# Lift2.net
KiCad netlist of a schematic drawn in EAGLE
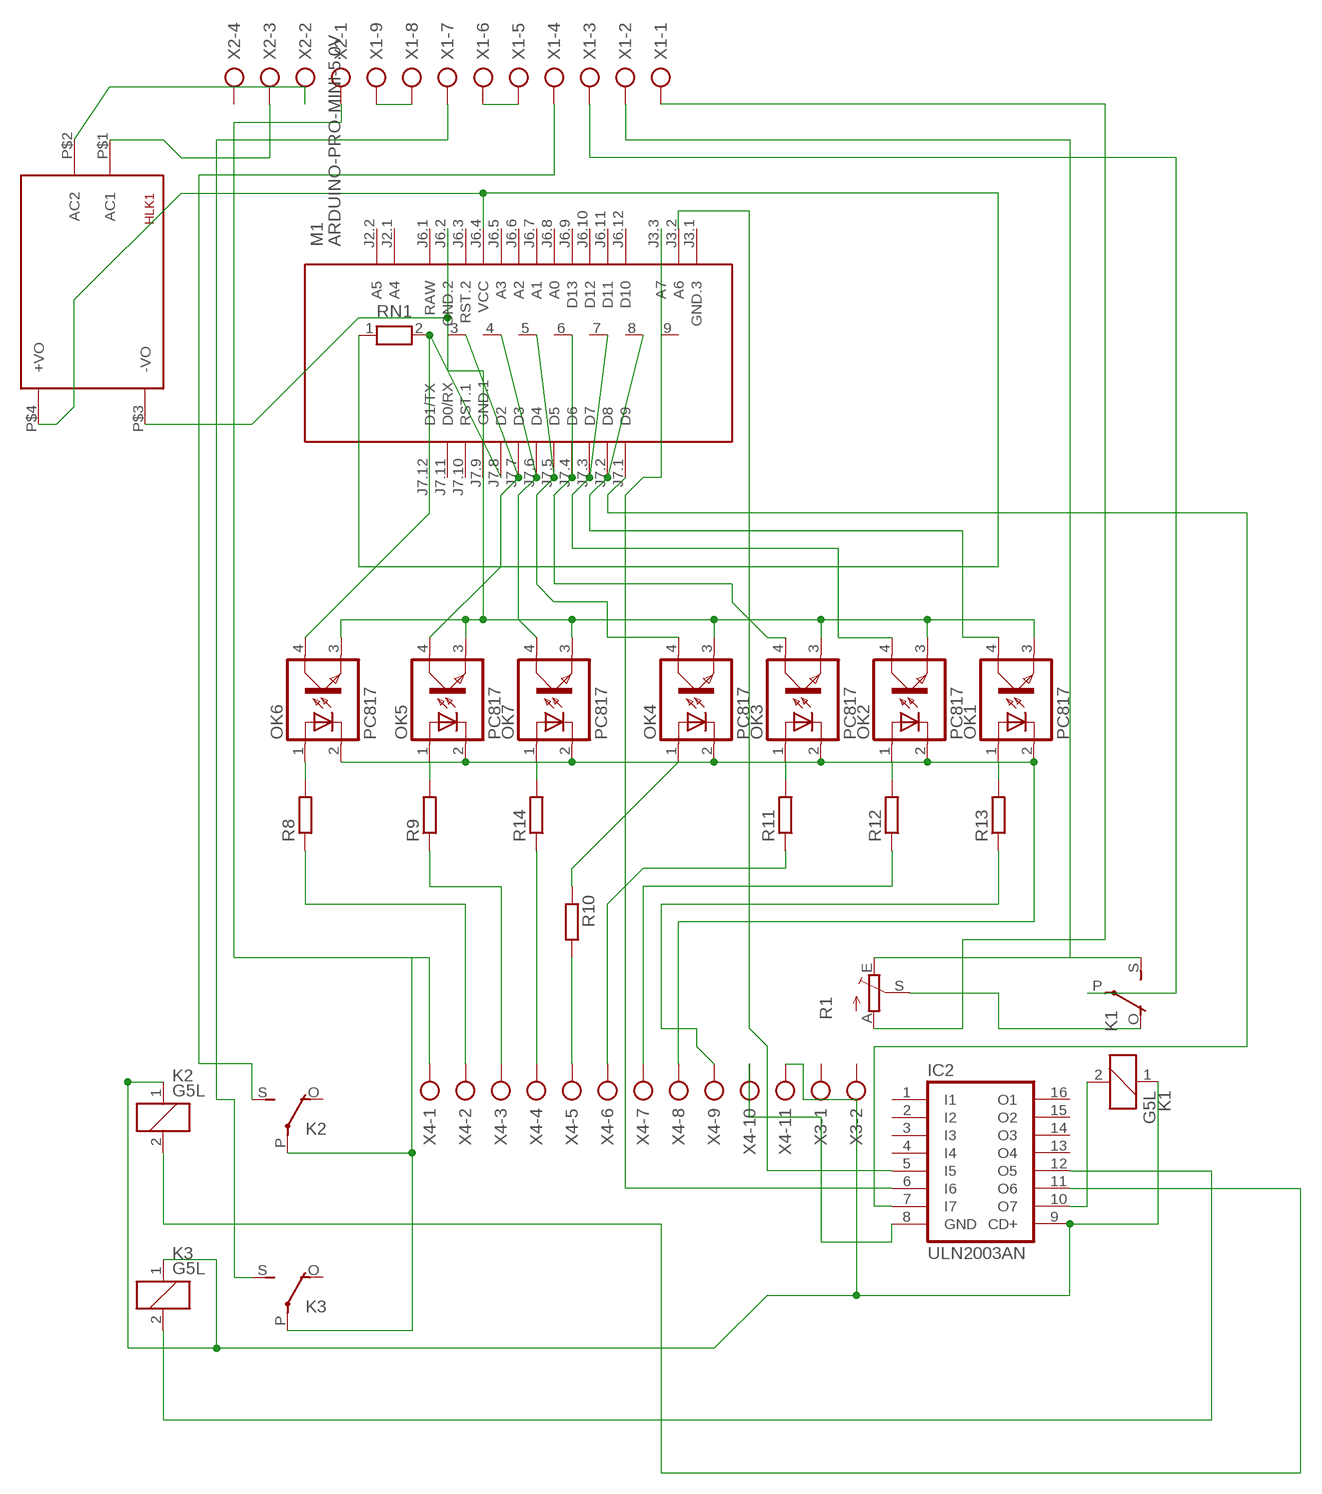
[diagram p0: schematic, sheet 1]

(export (version "E")
  (design (tool "Eeschema 10.0.6"))
  (components
    (comp (ref "HLK1")
      (value "HLK-PM013W")
      (footprint "eagle-import:HLK-PM01")
      (libsource (lib "eagle-import") (part "HLK-PM013W"))
    )
    (comp (ref "IC2")
      (value "ULN2003AN")
      (footprint "eagle-import:DIL16")
      (libsource (lib "eagle-import") (part "ULN2003AN"))
    )
    (comp (ref "K1")
      (value "G5L")
      (footprint "eagle-import:G5LE")
      (libsource (lib "eagle-import") (part "G5L"))
    )
    (comp (ref "K2")
      (value "G5L")
      (footprint "eagle-import:G5LE")
      (libsource (lib "eagle-import") (part "G5L"))
    )
    (comp (ref "K3")
      (value "G5L")
      (footprint "eagle-import:G5LE")
      (libsource (lib "eagle-import") (part "G5L"))
    )
    (comp (ref "M1")
      (value "ARDUINO-PRO-MINI-5.0V")
      (footprint "eagle-import:ARDUINO-PRO-MINI")
      (libsource (lib "eagle-import") (part "ARDUINO-PRO-MINI-5.0V"))
    )
    (comp (ref "OK1")
      (value "PC817")
      (footprint "eagle-import:DIL04")
      (fields (field (name "MPN") "PC817X4J000F"))
      (libsource (lib "eagle-import") (part "PC817"))
    )
    (comp (ref "OK2")
      (value "PC817")
      (footprint "eagle-import:DIL04")
      (fields (field (name "MPN") "PC817X4J000F"))
      (libsource (lib "eagle-import") (part "PC817"))
    )
    (comp (ref "OK3")
      (value "PC817")
      (footprint "eagle-import:DIL04")
      (fields (field (name "MPN") "PC817X4J000F"))
      (libsource (lib "eagle-import") (part "PC817"))
    )
    (comp (ref "OK4")
      (value "PC817")
      (footprint "eagle-import:DIL04")
      (fields (field (name "MPN") "PC817X4J000F"))
      (libsource (lib "eagle-import") (part "PC817"))
    )
    (comp (ref "OK5")
      (value "PC817")
      (footprint "eagle-import:DIL04")
      (fields (field (name "MPN") "PC817X4J000F"))
      (libsource (lib "eagle-import") (part "PC817"))
    )
    (comp (ref "OK6")
      (value "PC817")
      (footprint "eagle-import:DIL04")
      (fields (field (name "MPN") "PC817X4J000F"))
      (libsource (lib "eagle-import") (part "PC817"))
    )
    (comp (ref "OK7")
      (value "PC817")
      (footprint "eagle-import:DIL04")
      (fields (field (name "MPN") "PC817X4J000F"))
      (libsource (lib "eagle-import") (part "PC817"))
    )
    (comp (ref "R1")
      (value "TRIM_EU-CA6V")
      (footprint "eagle-import:CA6V")
      (libsource (lib "eagle-import") (part "TRIM_EU-CA6V"))
    )
    (comp (ref "R8")
      (value "R-EU_0204/7")
      (footprint "eagle-import:0204_7")
      (libsource (lib "eagle-import") (part "R-EU_0204/7"))
    )
    (comp (ref "R9")
      (value "R-EU_0204/7")
      (footprint "eagle-import:0204_7")
      (libsource (lib "eagle-import") (part "R-EU_0204/7"))
    )
    (comp (ref "R10")
      (value "R-EU_0204/7")
      (footprint "eagle-import:0204_7")
      (libsource (lib "eagle-import") (part "R-EU_0204/7"))
    )
    (comp (ref "R11")
      (value "R-EU_0204/7")
      (footprint "eagle-import:0204_7")
      (libsource (lib "eagle-import") (part "R-EU_0204/7"))
    )
    (comp (ref "R12")
      (value "R-EU_0204/7")
      (footprint "eagle-import:0204_7")
      (libsource (lib "eagle-import") (part "R-EU_0204/7"))
    )
    (comp (ref "R13")
      (value "R-EU_0204/7")
      (footprint "eagle-import:0204_7")
      (libsource (lib "eagle-import") (part "R-EU_0204/7"))
    )
    (comp (ref "R14")
      (value "R-EU_0204/7")
      (footprint "eagle-import:0204_7")
      (libsource (lib "eagle-import") (part "R-EU_0204/7"))
    )
    (comp (ref "RN1")
      (value "RN08")
      (footprint "eagle-import:RN-9")
      (libsource (lib "eagle-import") (part "RN08"))
    )
    (comp (ref "X1")
      (value "AK300/9")
      (footprint "eagle-import:AK300_9")
      (libsource (lib "eagle-import") (part "AK300/9"))
    )
    (comp (ref "X2")
      (value "AK300/4")
      (footprint "eagle-import:AK300_4")
      (libsource (lib "eagle-import") (part "AK300/4"))
    )
    (comp (ref "X3")
      (value "AK300/2")
      (footprint "eagle-import:AK300_2")
      (libsource (lib "eagle-import") (part "AK300/2"))
    )
    (comp (ref "X4")
      (value "AK300/11")
      (footprint "eagle-import:AK300_11")
      (libsource (lib "eagle-import") (part "AK300/11"))
    )
  )
  (nets
    (net (code "1") (name "/RAW") (class "Default")
      (node (ref "M1") (pin "J6.1") (pinfunction "RAW_J6.1") (pintype "power_in"))
    )
    (net (code "2") (name "Net-(HLK1-+VO)") (class "Default")
      (node (ref "HLK1") (pin "P$4") (pinfunction "+VO_P$4") (pintype "bidirectional"))
      (node (ref "M1") (pin "J6.4") (pinfunction "VCC_J6.4") (pintype "power_in"))
      (node (ref "RN1") (pin "1") (pinfunction "1_1") (pintype "passive"))
    )
    (net (code "3") (name "Net-(HLK1--VO)") (class "Default")
      (node (ref "HLK1") (pin "P$3") (pinfunction "-VO_P$3") (pintype "bidirectional"))
      (node (ref "M1") (pin "J6.2") (pinfunction "GND.2_J6.2") (pintype "power_in"))
      (node (ref "M1") (pin "J7.9") (pinfunction "GND.1_J7.9") (pintype "power_in"))
      (node (ref "OK1") (pin "3") (pinfunction "EMIT_3") (pintype "passive"))
      (node (ref "OK2") (pin "3") (pinfunction "EMIT_3") (pintype "passive"))
      (node (ref "OK3") (pin "3") (pinfunction "EMIT_3") (pintype "passive"))
      (node (ref "OK4") (pin "3") (pinfunction "EMIT_3") (pintype "passive"))
      (node (ref "OK5") (pin "3") (pinfunction "EMIT_3") (pintype "passive"))
      (node (ref "OK6") (pin "3") (pinfunction "EMIT_3") (pintype "passive"))
      (node (ref "OK7") (pin "3") (pinfunction "EMIT_3") (pintype "passive"))
    )
    (net (code "4") (name "Net-(HLK1-AC1)") (class "Default")
      (node (ref "HLK1") (pin "P$1") (pinfunction "AC1_P$1") (pintype "bidirectional"))
      (node (ref "X2") (pin "3") (pinfunction "KL_3") (pintype "passive"))
    )
    (net (code "5") (name "Net-(HLK1-AC2)") (class "Default")
      (node (ref "HLK1") (pin "P$2") (pinfunction "AC2_P$2") (pintype "bidirectional"))
      (node (ref "X2") (pin "2") (pinfunction "KL_2") (pintype "passive"))
    )
    (net (code "6") (name "Net-(IC2-CD+)") (class "Default")
      (node (ref "IC2") (pin "9") (pinfunction "CD+_9") (pintype "passive"))
      (node (ref "K1") (pin "1") (pinfunction "1_1") (pintype "passive"))
      (node (ref "K2") (pin "1") (pinfunction "1_1") (pintype "passive"))
      (node (ref "K3") (pin "1") (pinfunction "1_1") (pintype "passive"))
      (node (ref "X4") (pin "11") (pinfunction "KL_11") (pintype "passive"))
    )
    (net (code "7") (name "Net-(IC2-GND)") (class "Default")
      (node (ref "IC2") (pin "8") (pinfunction "GND_8") (pintype "power_in"))
      (node (ref "X4") (pin "10") (pinfunction "KL_10") (pintype "passive"))
    )
    (net (code "8") (name "Net-(IC2-I5)") (class "Default")
      (node (ref "IC2") (pin "5") (pinfunction "I5_5") (pintype "input"))
      (node (ref "M1") (pin "J3.2") (pinfunction "A6_J3.2") (pintype "bidirectional"))
    )
    (net (code "9") (name "Net-(IC2-I6)") (class "Default")
      (node (ref "IC2") (pin "6") (pinfunction "I6_6") (pintype "input"))
      (node (ref "M1") (pin "J3.3") (pinfunction "A7_J3.3") (pintype "bidirectional"))
    )
    (net (code "10") (name "Net-(IC2-I7)") (class "Default")
      (node (ref "IC2") (pin "7") (pinfunction "I7_7") (pintype "input"))
      (node (ref "M1") (pin "J7.1") (pinfunction "D9_J7.1") (pintype "bidirectional"))
    )
    (net (code "11") (name "Net-(IC2-O5)") (class "Default")
      (node (ref "IC2") (pin "12") (pinfunction "O5_12") (pintype "open_collector"))
      (node (ref "K3") (pin "2") (pinfunction "2_2") (pintype "passive"))
    )
    (net (code "12") (name "Net-(IC2-O6)") (class "Default")
      (node (ref "IC2") (pin "11") (pinfunction "O6_11") (pintype "open_collector"))
      (node (ref "K2") (pin "2") (pinfunction "2_2") (pintype "passive"))
    )
    (net (code "13") (name "Net-(IC2-O7)") (class "Default")
      (node (ref "IC2") (pin "10") (pinfunction "O7_10") (pintype "open_collector"))
      (node (ref "K1") (pin "2") (pinfunction "2_2") (pintype "passive"))
    )
    (net (code "14") (name "Net-(K1-PadO)") (class "Default")
      (node (ref "K1") (pin "O") (pinfunction "O_O") (pintype "passive"))
      (node (ref "R1") (pin "S") (pinfunction "S_S") (pintype "passive"))
    )
    (net (code "15") (name "Net-(M1-D2)") (class "Default")
      (node (ref "M1") (pin "J7.8") (pinfunction "D2_J7.8") (pintype "bidirectional"))
      (node (ref "OK6") (pin "4") (pinfunction "COL_4") (pintype "passive"))
      (node (ref "RN1") (pin "2") (pinfunction "2_2") (pintype "passive"))
    )
    (net (code "16") (name "Net-(M1-D3)") (class "Default")
      (node (ref "M1") (pin "J7.7") (pinfunction "D3_J7.7") (pintype "bidirectional"))
      (node (ref "OK5") (pin "4") (pinfunction "COL_4") (pintype "passive"))
      (node (ref "RN1") (pin "3") (pinfunction "3_3") (pintype "passive"))
    )
    (net (code "17") (name "Net-(M1-D4)") (class "Default")
      (node (ref "M1") (pin "J7.6") (pinfunction "D4_J7.6") (pintype "bidirectional"))
      (node (ref "OK7") (pin "4") (pinfunction "COL_4") (pintype "passive"))
      (node (ref "RN1") (pin "4") (pinfunction "4_4") (pintype "passive"))
    )
    (net (code "18") (name "Net-(M1-D5)") (class "Default")
      (node (ref "M1") (pin "J7.5") (pinfunction "D5_J7.5") (pintype "bidirectional"))
      (node (ref "OK4") (pin "4") (pinfunction "COL_4") (pintype "passive"))
      (node (ref "RN1") (pin "5") (pinfunction "5_5") (pintype "passive"))
    )
    (net (code "19") (name "Net-(M1-D6)") (class "Default")
      (node (ref "M1") (pin "J7.4") (pinfunction "D6_J7.4") (pintype "bidirectional"))
      (node (ref "OK3") (pin "4") (pinfunction "COL_4") (pintype "passive"))
      (node (ref "RN1") (pin "6") (pinfunction "6_6") (pintype "passive"))
    )
    (net (code "20") (name "Net-(M1-D7)") (class "Default")
      (node (ref "M1") (pin "J7.3") (pinfunction "D7_J7.3") (pintype "bidirectional"))
      (node (ref "OK2") (pin "4") (pinfunction "COL_4") (pintype "passive"))
      (node (ref "RN1") (pin "7") (pinfunction "7_7") (pintype "passive"))
    )
    (net (code "21") (name "Net-(M1-D8)") (class "Default")
      (node (ref "M1") (pin "J7.2") (pinfunction "D8_J7.2") (pintype "bidirectional"))
      (node (ref "OK1") (pin "4") (pinfunction "COL_4") (pintype "passive"))
      (node (ref "RN1") (pin "8") (pinfunction "8_8") (pintype "passive"))
    )
    (net (code "22") (name "Net-(OK1-A)") (class "Default")
      (node (ref "OK1") (pin "1") (pinfunction "A_1") (pintype "passive"))
      (node (ref "R13") (pin "2") (pinfunction "2_2") (pintype "passive"))
    )
    (net (code "23") (name "Net-(OK1-C)") (class "Default")
      (node (ref "OK1") (pin "2") (pinfunction "C_2") (pintype "passive"))
      (node (ref "OK2") (pin "2") (pinfunction "C_2") (pintype "passive"))
      (node (ref "OK3") (pin "2") (pinfunction "C_2") (pintype "passive"))
      (node (ref "OK4") (pin "2") (pinfunction "C_2") (pintype "passive"))
      (node (ref "OK5") (pin "2") (pinfunction "C_2") (pintype "passive"))
      (node (ref "OK6") (pin "2") (pinfunction "C_2") (pintype "passive"))
      (node (ref "OK7") (pin "2") (pinfunction "C_2") (pintype "passive"))
      (node (ref "X4") (pin "8") (pinfunction "KL_8") (pintype "passive"))
    )
    (net (code "24") (name "Net-(OK2-A)") (class "Default")
      (node (ref "OK2") (pin "1") (pinfunction "A_1") (pintype "passive"))
      (node (ref "R12") (pin "2") (pinfunction "2_2") (pintype "passive"))
    )
    (net (code "25") (name "Net-(OK3-A)") (class "Default")
      (node (ref "OK3") (pin "1") (pinfunction "A_1") (pintype "passive"))
      (node (ref "R11") (pin "2") (pinfunction "2_2") (pintype "passive"))
    )
    (net (code "26") (name "Net-(OK4-A)") (class "Default")
      (node (ref "OK4") (pin "1") (pinfunction "A_1") (pintype "passive"))
      (node (ref "R10") (pin "1") (pinfunction "1_1") (pintype "passive"))
    )
    (net (code "27") (name "Net-(OK5-A)") (class "Default")
      (node (ref "OK5") (pin "1") (pinfunction "A_1") (pintype "passive"))
      (node (ref "R9") (pin "2") (pinfunction "2_2") (pintype "passive"))
    )
    (net (code "28") (name "Net-(OK6-A)") (class "Default")
      (node (ref "OK6") (pin "1") (pinfunction "A_1") (pintype "passive"))
      (node (ref "R8") (pin "2") (pinfunction "2_2") (pintype "passive"))
    )
    (net (code "29") (name "Net-(OK7-A)") (class "Default")
      (node (ref "OK7") (pin "1") (pinfunction "A_1") (pintype "passive"))
      (node (ref "R14") (pin "2") (pinfunction "2_2") (pintype "passive"))
    )
    (net (code "30") (name "Net-(X1A-KL)") (class "Default")
      (node (ref "R1") (pin "A") (pinfunction "A_A") (pintype "passive"))
      (node (ref "X1") (pin "1") (pinfunction "KL_1") (pintype "passive"))
    )
    (net (code "31") (name "Net-(X1B-KL)") (class "Default")
      (node (ref "K1") (pin "S") (pinfunction "S_S") (pintype "passive"))
      (node (ref "R1") (pin "E") (pinfunction "E_E") (pintype "passive"))
      (node (ref "X1") (pin "2") (pinfunction "KL_2") (pintype "passive"))
    )
    (net (code "32") (name "Net-(X1C-KL)") (class "Default")
      (node (ref "K1") (pin "P") (pinfunction "P_P") (pintype "passive"))
      (node (ref "X1") (pin "3") (pinfunction "KL_3") (pintype "passive"))
    )
    (net (code "33") (name "Net-(X1D-KL)") (class "Default")
      (node (ref "K2") (pin "S") (pinfunction "S_S") (pintype "passive"))
      (node (ref "X1") (pin "4") (pinfunction "KL_4") (pintype "passive"))
    )
    (net (code "34") (name "Net-(X1E-KL)") (class "Default")
      (node (ref "X1") (pin "5") (pinfunction "KL_5") (pintype "passive"))
      (node (ref "X1") (pin "6") (pinfunction "KL_6") (pintype "passive"))
    )
    (net (code "35") (name "Net-(X1G-KL)") (class "Default")
      (node (ref "K3") (pin "S") (pinfunction "S_S") (pintype "passive"))
      (node (ref "X1") (pin "7") (pinfunction "KL_7") (pintype "passive"))
    )
    (net (code "36") (name "Net-(X1H-KL)") (class "Default")
      (node (ref "X1") (pin "8") (pinfunction "KL_8") (pintype "passive"))
      (node (ref "X1") (pin "9") (pinfunction "KL_9") (pintype "passive"))
    )
    (net (code "37") (name "Net-(X2A-KL)") (class "Default")
      (node (ref "K2") (pin "P") (pinfunction "P_P") (pintype "passive"))
      (node (ref "K3") (pin "P") (pinfunction "P_P") (pintype "passive"))
      (node (ref "X2") (pin "1") (pinfunction "KL_1") (pintype "passive"))
      (node (ref "X4") (pin "1") (pinfunction "KL_1") (pintype "passive"))
    )
    (net (code "38") (name "Net-(X4D-KL)") (class "Default")
      (node (ref "R8") (pin "1") (pinfunction "1_1") (pintype "passive"))
      (node (ref "X4") (pin "2") (pinfunction "KL_2") (pintype "passive"))
    )
    (net (code "39") (name "Net-(X4E-KL)") (class "Default")
      (node (ref "R9") (pin "1") (pinfunction "1_1") (pintype "passive"))
      (node (ref "X4") (pin "3") (pinfunction "KL_3") (pintype "passive"))
    )
    (net (code "40") (name "Net-(X4F-KL)") (class "Default")
      (node (ref "R14") (pin "1") (pinfunction "1_1") (pintype "passive"))
      (node (ref "X4") (pin "4") (pinfunction "KL_4") (pintype "passive"))
    )
    (net (code "41") (name "Net-(X4G-KL)") (class "Default")
      (node (ref "R10") (pin "2") (pinfunction "2_2") (pintype "passive"))
      (node (ref "X4") (pin "5") (pinfunction "KL_5") (pintype "passive"))
    )
    (net (code "42") (name "Net-(X4H-KL)") (class "Default")
      (node (ref "R11") (pin "1") (pinfunction "1_1") (pintype "passive"))
      (node (ref "X4") (pin "6") (pinfunction "KL_6") (pintype "passive"))
    )
    (net (code "43") (name "Net-(X4I-KL)") (class "Default")
      (node (ref "R12") (pin "1") (pinfunction "1_1") (pintype "passive"))
      (node (ref "X4") (pin "7") (pinfunction "KL_7") (pintype "passive"))
    )
    (net (code "44") (name "Net-(X4K-KL)") (class "Default")
      (node (ref "R13") (pin "1") (pinfunction "1_1") (pintype "passive"))
      (node (ref "X4") (pin "9") (pinfunction "KL_9") (pintype "passive"))
    )
    (net (code "45") (name "unconnected-(IC2-I1-Pad1)") (class "Default")
      (node (ref "IC2") (pin "1") (pinfunction "I1_1") (pintype "input"))
    )
    (net (code "46") (name "unconnected-(IC2-I2-Pad2)") (class "Default")
      (node (ref "IC2") (pin "2") (pinfunction "I2_2") (pintype "input"))
    )
    (net (code "47") (name "unconnected-(IC2-I3-Pad3)") (class "Default")
      (node (ref "IC2") (pin "3") (pinfunction "I3_3") (pintype "input"))
    )
    (net (code "48") (name "unconnected-(IC2-I4-Pad4)") (class "Default")
      (node (ref "IC2") (pin "4") (pinfunction "I4_4") (pintype "input"))
    )
    (net (code "49") (name "unconnected-(IC2-O1-Pad16)") (class "Default")
      (node (ref "IC2") (pin "16") (pinfunction "O1_16") (pintype "open_collector"))
    )
    (net (code "50") (name "unconnected-(IC2-O2-Pad15)") (class "Default")
      (node (ref "IC2") (pin "15") (pinfunction "O2_15") (pintype "open_collector"))
    )
    (net (code "51") (name "unconnected-(IC2-O3-Pad14)") (class "Default")
      (node (ref "IC2") (pin "14") (pinfunction "O3_14") (pintype "open_collector"))
    )
    (net (code "52") (name "unconnected-(IC2-O4-Pad13)") (class "Default")
      (node (ref "IC2") (pin "13") (pinfunction "O4_13") (pintype "open_collector"))
    )
    (net (code "53") (name "unconnected-(K2-PadO)") (class "Default")
      (node (ref "K2") (pin "O") (pinfunction "O_O") (pintype "passive"))
    )
    (net (code "54") (name "unconnected-(K3-PadO)") (class "Default")
      (node (ref "K3") (pin "O") (pinfunction "O_O") (pintype "passive"))
    )
    (net (code "55") (name "unconnected-(M1-A0-PadJ6.8)") (class "Default")
      (node (ref "M1") (pin "J6.8") (pinfunction "A0_J6.8") (pintype "bidirectional"))
    )
    (net (code "56") (name "unconnected-(M1-A1-PadJ6.7)") (class "Default")
      (node (ref "M1") (pin "J6.7") (pinfunction "A1_J6.7") (pintype "bidirectional"))
    )
    (net (code "57") (name "unconnected-(M1-A2-PadJ6.6)") (class "Default")
      (node (ref "M1") (pin "J6.6") (pinfunction "A2_J6.6") (pintype "bidirectional"))
    )
    (net (code "58") (name "unconnected-(M1-A3-PadJ6.5)") (class "Default")
      (node (ref "M1") (pin "J6.5") (pinfunction "A3_J6.5") (pintype "bidirectional"))
    )
    (net (code "59") (name "unconnected-(M1-A4-PadJ2.1)") (class "Default")
      (node (ref "M1") (pin "J2.1") (pinfunction "A4_J2.1") (pintype "bidirectional"))
    )
    (net (code "60") (name "unconnected-(M1-A5-PadJ2.2)") (class "Default")
      (node (ref "M1") (pin "J2.2") (pinfunction "A5_J2.2") (pintype "bidirectional"))
    )
    (net (code "61") (name "unconnected-(M1-D0{slash}RX-PadJ7.11)") (class "Default")
      (node (ref "M1") (pin "J7.11") (pinfunction "D0/RX_J7.11") (pintype "bidirectional"))
    )
    (net (code "62") (name "unconnected-(M1-D1{slash}TX-PadJ7.12)") (class "Default")
      (node (ref "M1") (pin "J7.12") (pinfunction "D1/TX_J7.12") (pintype "bidirectional"))
    )
    (net (code "63") (name "unconnected-(M1-D10-PadJ6.12)") (class "Default")
      (node (ref "M1") (pin "J6.12") (pinfunction "D10_J6.12") (pintype "bidirectional"))
    )
    (net (code "64") (name "unconnected-(M1-D11-PadJ6.11)") (class "Default")
      (node (ref "M1") (pin "J6.11") (pinfunction "D11_J6.11") (pintype "bidirectional"))
    )
    (net (code "65") (name "unconnected-(M1-D12-PadJ6.10)") (class "Default")
      (node (ref "M1") (pin "J6.10") (pinfunction "D12_J6.10") (pintype "bidirectional"))
    )
    (net (code "66") (name "unconnected-(M1-D13-PadJ6.9)") (class "Default")
      (node (ref "M1") (pin "J6.9") (pinfunction "D13_J6.9") (pintype "bidirectional"))
    )
    (net (code "67") (name "unconnected-(M1-GND.3-PadJ3.1)") (class "Default")
      (node (ref "M1") (pin "J3.1") (pinfunction "GND.3_J3.1") (pintype "bidirectional"))
    )
    (net (code "68") (name "unconnected-(M1-RST.1-PadJ7.10)") (class "Default")
      (node (ref "M1") (pin "J7.10") (pinfunction "RST.1_J7.10") (pintype "bidirectional"))
    )
    (net (code "69") (name "unconnected-(M1-RST.2-PadJ6.3)") (class "Default")
      (node (ref "M1") (pin "J6.3") (pinfunction "RST.2_J6.3") (pintype "bidirectional"))
    )
    (net (code "70") (name "unconnected-(RN1-Pad9)") (class "Default")
      (node (ref "RN1") (pin "9") (pinfunction "9_9") (pintype "passive"))
    )
    (net (code "71") (name "unconnected-(X2D-KL-Pad4)") (class "Default")
      (node (ref "X2") (pin "4") (pinfunction "KL_4") (pintype "passive"))
    )
    (net (code "72") (name "unconnected-(X3A-KL-Pad1)") (class "Default")
      (node (ref "X3") (pin "1") (pinfunction "KL_1") (pintype "passive"))
    )
    (net (code "73") (name "unconnected-(X3B-KL-Pad2)") (class "Default")
      (node (ref "X3") (pin "2") (pinfunction "KL_2") (pintype "passive"))
    )
  )
)
